# armwiz-board.net
KiCad netlist of a schematic drawn in EAGLE
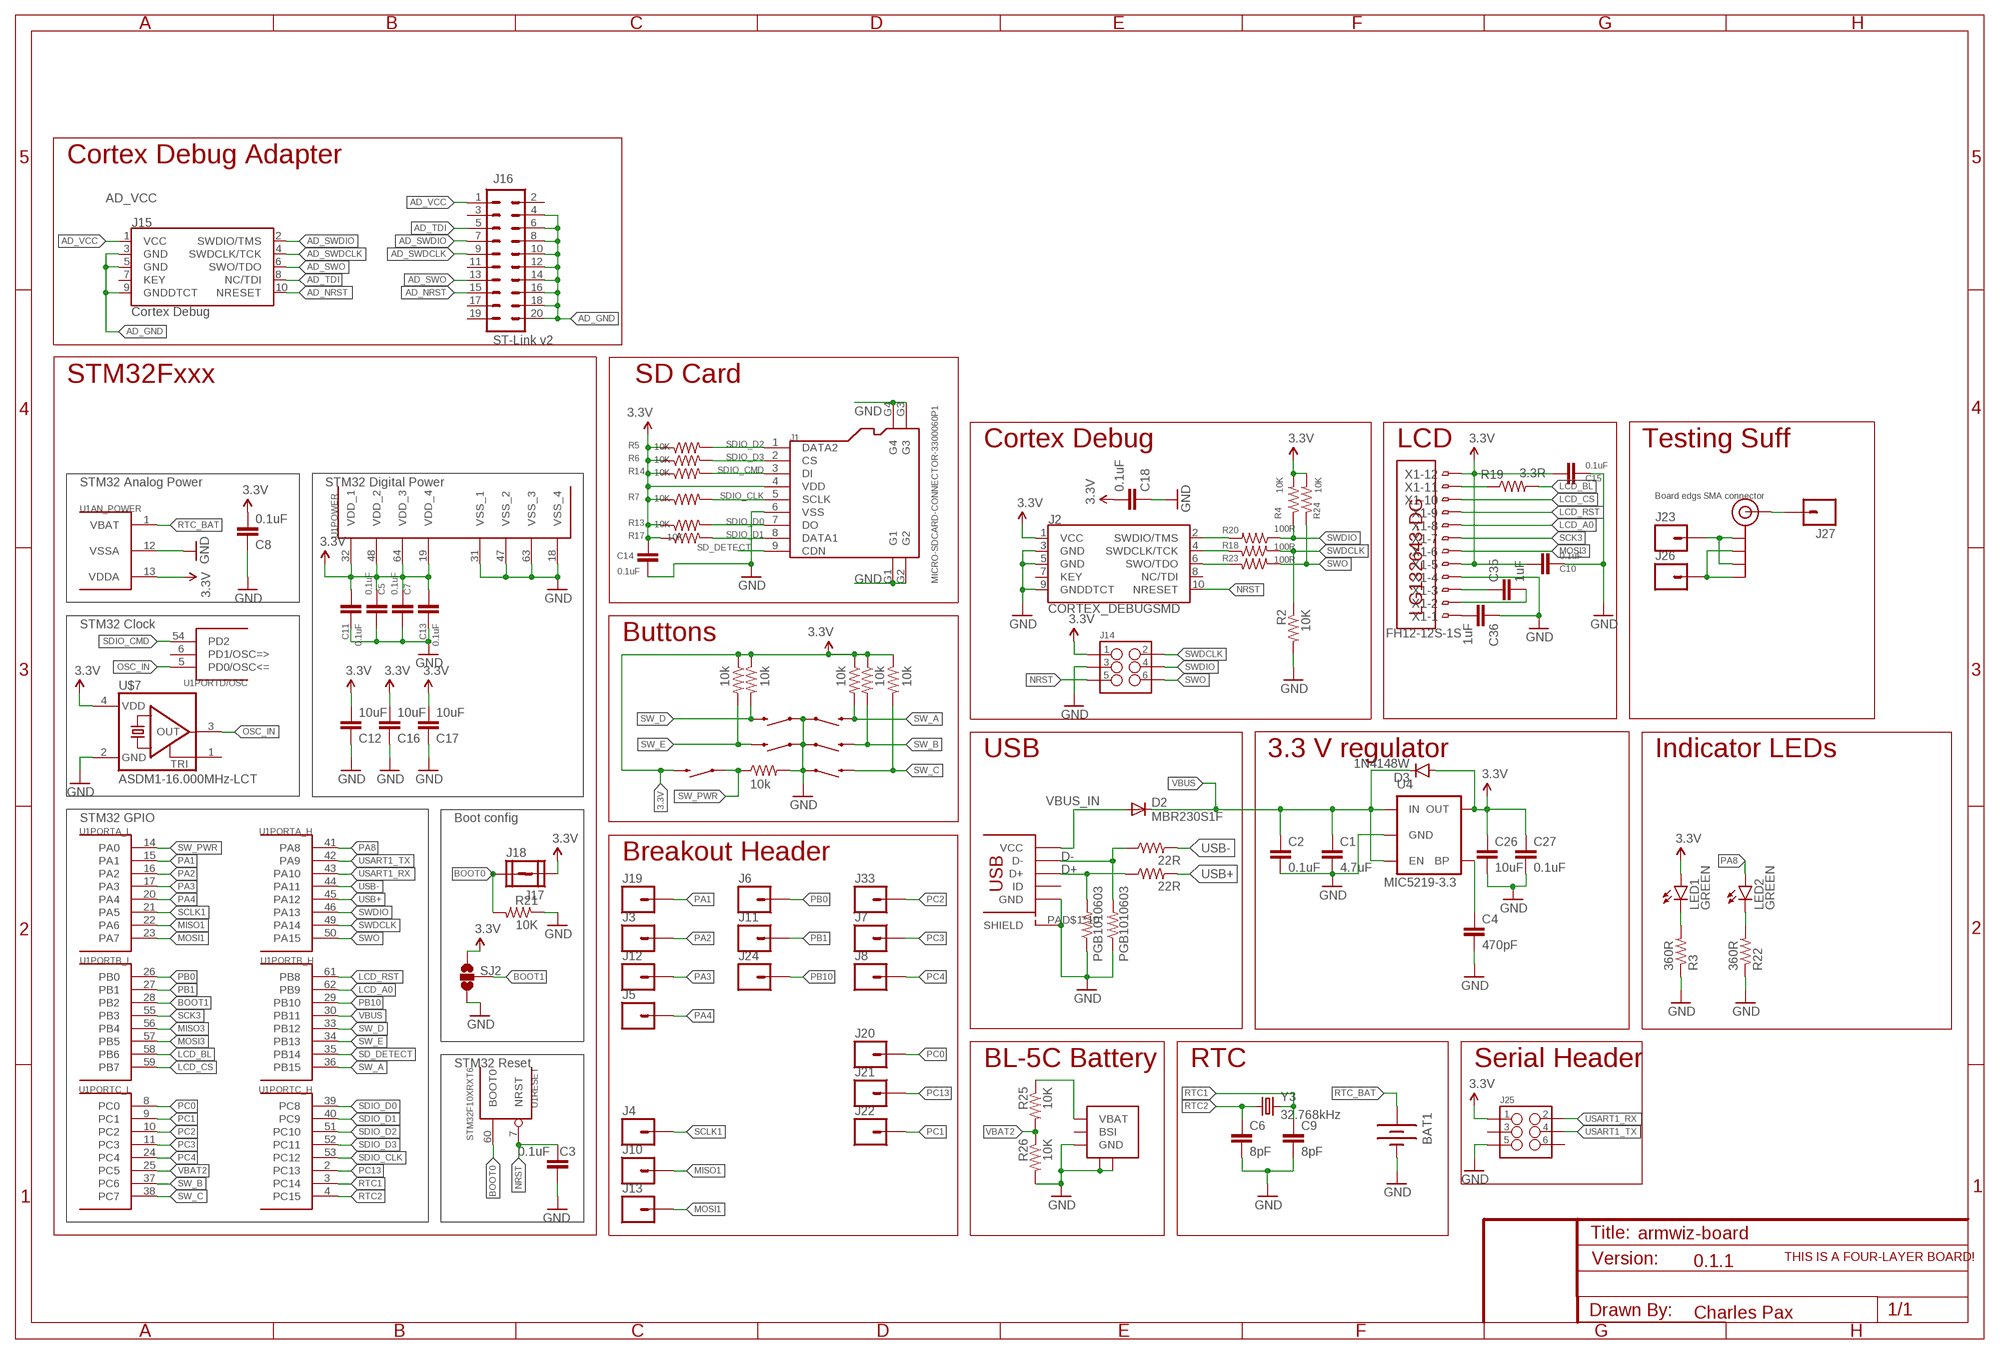
[diagram p0: schematic, sheet 1]

(export (version "E")
  (design (tool "Eeschema 10.0.6"))
  (components
    (comp (ref "BAT1")
      (value "BATTERY12MM")
      (footprint "eagle-import:BATTCON_12MM")
      (fields (field (name "MF") "Keystone Electronics") (field (name "MPN") "3000TR"))
      (libsource (lib "eagle-import") (part "BATTERY12MM"))
    )
    (comp (ref "C1")
      (value "4.7uF")
      (footprint "eagle-import:C0402K")
      (libsource (lib "eagle-import") (part "C-EUC0402K"))
    )
    (comp (ref "C2")
      (value "0.1uF")
      (footprint "eagle-import:C0402K")
      (libsource (lib "eagle-import") (part "C-EUC0402K"))
    )
    (comp (ref "C3")
      (value "0.1uF")
      (footprint "eagle-import:C0402K")
      (libsource (lib "eagle-import") (part "C-EUC0402K"))
    )
    (comp (ref "C4")
      (value "470pF")
      (footprint "eagle-import:C0402K")
      (libsource (lib "eagle-import") (part "C-EUC0402K"))
    )
    (comp (ref "C5")
      (value "0.1uF")
      (footprint "eagle-import:C0402K")
      (libsource (lib "eagle-import") (part "C-EUC0402K"))
    )
    (comp (ref "C6")
      (value "8pF")
      (footprint "eagle-import:C0402K")
      (libsource (lib "eagle-import") (part "C-EUC0402K"))
    )
    (comp (ref "C7")
      (value "0.1uF")
      (footprint "eagle-import:C0402K")
      (libsource (lib "eagle-import") (part "C-EUC0402K"))
    )
    (comp (ref "C8")
      (value "0.1uF")
      (footprint "eagle-import:C0402K")
      (libsource (lib "eagle-import") (part "C-EUC0402K"))
    )
    (comp (ref "C9")
      (value "8pF")
      (footprint "eagle-import:C0402K")
      (libsource (lib "eagle-import") (part "C-EUC0402K"))
    )
    (comp (ref "C10")
      (value "0.1uF")
      (footprint "eagle-import:C0402K")
      (libsource (lib "eagle-import") (part "C-EUC0402K"))
    )
    (comp (ref "C11")
      (value "0.1uF")
      (footprint "eagle-import:C0402K")
      (libsource (lib "eagle-import") (part "C-EUC0402K"))
    )
    (comp (ref "C12")
      (value "10uF")
      (footprint "eagle-import:C0402K")
      (libsource (lib "eagle-import") (part "C-EUC0402K"))
    )
    (comp (ref "C13")
      (value "0.1uF")
      (footprint "eagle-import:C0402K")
      (libsource (lib "eagle-import") (part "C-EUC0402K"))
    )
    (comp (ref "C14")
      (value "0.1uF")
      (footprint "eagle-import:C0402K")
      (libsource (lib "eagle-import") (part "C-EUC0402K"))
    )
    (comp (ref "C15")
      (value "0.1uF")
      (footprint "eagle-import:C0402K")
      (libsource (lib "eagle-import") (part "C-EUC0402K"))
    )
    (comp (ref "C16")
      (value "10uF")
      (footprint "eagle-import:C0402K")
      (libsource (lib "eagle-import") (part "C-EUC0402K"))
    )
    (comp (ref "C17")
      (value "10uF")
      (footprint "eagle-import:C0402K")
      (libsource (lib "eagle-import") (part "C-EUC0402K"))
    )
    (comp (ref "C18")
      (value "0.1uF")
      (footprint "eagle-import:C0402K")
      (libsource (lib "eagle-import") (part "C-EUC0402K"))
    )
    (comp (ref "C26")
      (value "10uF")
      (footprint "eagle-import:C0402K")
      (libsource (lib "eagle-import") (part "C-EUC0402K"))
    )
    (comp (ref "C27")
      (value "0.1uF")
      (footprint "eagle-import:C0402K")
      (libsource (lib "eagle-import") (part "C-EUC0402K"))
    )
    (comp (ref "C35")
      (value "1uF")
      (footprint "eagle-import:C0402K")
      (libsource (lib "eagle-import") (part "C-EUC0402K"))
    )
    (comp (ref "C36")
      (value "1uF")
      (footprint "eagle-import:C0402K")
      (libsource (lib "eagle-import") (part "C-EUC0402K"))
    )
    (comp (ref "D2")
      (value "MBR230S1F")
      (footprint "eagle-import:SOD123")
      (fields (field (name "MF") "DIODES INC") (field (name "MPN") "MBR230S1F-7"))
      (libsource (lib "eagle-import") (part "SPARKFUN-DISCRETESEMI_DIODESOD123SOD123"))
    )
    (comp (ref "D3")
      (value "1N4148W")
      (footprint "eagle-import:SOD-123")
      (libsource (lib "eagle-import") (part "DIODESOD123"))
    )
    (comp (ref "J$1")
      (value "SMA_EDGE")
      (footprint "eagle-import:SMA-EDGE")
      (libsource (lib "eagle-import") (part "SMA_EDGE"))
    )
    (comp (ref "J1")
      (value "MICRO-SDCARD-CONNECTOR-3300060P1")
      (footprint "eagle-import:9P-SMD-W-RING")
      (fields (field (name "MF") "SUNTECH") (field (name "MPN") "ST-TF-003A"))
      (libsource (lib "eagle-import") (part "MICRO-SDCARD-CONNECTOR-3300060P1"))
    )
    (comp (ref "J2")
      (value "CORTEX_DEBUGSMD")
      (footprint "eagle-import:SAMTECH_FTSH-105-01")
      (libsource (lib "eagle-import") (part "CORTEX_DEBUGSMD"))
    )
    (comp (ref "J3")
      (value "M01PTH")
      (footprint "eagle-import:1X01")
      (libsource (lib "eagle-import") (part "M01PTH"))
    )
    (comp (ref "J4")
      (value "M01PTH")
      (footprint "eagle-import:1X01")
      (libsource (lib "eagle-import") (part "M01PTH"))
    )
    (comp (ref "J5")
      (value "M01PTH")
      (footprint "eagle-import:1X01")
      (libsource (lib "eagle-import") (part "M01PTH"))
    )
    (comp (ref "J6")
      (value "M01PTH")
      (footprint "eagle-import:1X01")
      (libsource (lib "eagle-import") (part "M01PTH"))
    )
    (comp (ref "J7")
      (value "M01PTH")
      (footprint "eagle-import:1X01")
      (libsource (lib "eagle-import") (part "M01PTH"))
    )
    (comp (ref "J8")
      (value "M01PTH")
      (footprint "eagle-import:1X01")
      (libsource (lib "eagle-import") (part "M01PTH"))
    )
    (comp (ref "J10")
      (value "M01PTH")
      (footprint "eagle-import:1X01")
      (libsource (lib "eagle-import") (part "M01PTH"))
    )
    (comp (ref "J11")
      (value "M01PTH")
      (footprint "eagle-import:1X01")
      (libsource (lib "eagle-import") (part "M01PTH"))
    )
    (comp (ref "J12")
      (value "M01PTH")
      (footprint "eagle-import:1X01")
      (libsource (lib "eagle-import") (part "M01PTH"))
    )
    (comp (ref "J13")
      (value "M01PTH")
      (footprint "eagle-import:1X01")
      (libsource (lib "eagle-import") (part "M01PTH"))
    )
    (comp (ref "J14")
      (value "M03X2PAX")
      (footprint "eagle-import:CONNECTORS_2X3_SMT_POSTS_T400")
      (fields (field (name "MF") "FCI") (field (name "MPN") "95278-101A06LF"))
      (libsource (lib "eagle-import") (part "M03X2PAX"))
    )
    (comp (ref "J15")
      (value "Cortex Debug")
      (footprint "eagle-import:SAMTECH_FTSH-105-01")
      (libsource (lib "eagle-import") (part "CORTEX_DEBUGSMD"))
    )
    (comp (ref "J16")
      (value "ST-Link v2")
      (footprint "eagle-import:2X10")
      (libsource (lib "eagle-import") (part "M10X2"))
    )
    (comp (ref "J17")
      (value "M01NOSILK-KIT")
      (footprint "eagle-import:1X01NS-KIT")
      (libsource (lib "eagle-import") (part "M01NOSILK-KIT"))
    )
    (comp (ref "J18")
      (value "M01NOSILK-KIT")
      (footprint "eagle-import:1X01NS-KIT")
      (libsource (lib "eagle-import") (part "M01NOSILK-KIT"))
    )
    (comp (ref "J19")
      (value "M01PTH")
      (footprint "eagle-import:1X01")
      (libsource (lib "eagle-import") (part "M01PTH"))
    )
    (comp (ref "J20")
      (value "M01PTH")
      (footprint "eagle-import:1X01")
      (libsource (lib "eagle-import") (part "M01PTH"))
    )
    (comp (ref "J21")
      (value "M01PTH")
      (footprint "eagle-import:1X01")
      (libsource (lib "eagle-import") (part "M01PTH"))
    )
    (comp (ref "J22")
      (value "M01PTH")
      (footprint "eagle-import:1X01")
      (libsource (lib "eagle-import") (part "M01PTH"))
    )
    (comp (ref "J23")
      (value "M01PTH")
      (footprint "eagle-import:1X01")
      (libsource (lib "eagle-import") (part "M01PTH"))
    )
    (comp (ref "J24")
      (value "M01PTH")
      (footprint "eagle-import:1X01")
      (libsource (lib "eagle-import") (part "M01PTH"))
    )
    (comp (ref "J25")
      (value "M03X2PAX")
      (footprint "eagle-import:CONNECTORS_2X3_SMT_POSTS_T400")
      (fields (field (name "MF") "FCI") (field (name "MPN") "95278-101A06LF"))
      (libsource (lib "eagle-import") (part "M03X2PAX"))
    )
    (comp (ref "J26")
      (value "M01PTH")
      (footprint "eagle-import:1X01")
      (libsource (lib "eagle-import") (part "M01PTH"))
    )
    (comp (ref "J27")
      (value "M01PTH")
      (footprint "eagle-import:1X01")
      (libsource (lib "eagle-import") (part "M01PTH"))
    )
    (comp (ref "J33")
      (value "M01PTH")
      (footprint "eagle-import:1X01")
      (libsource (lib "eagle-import") (part "M01PTH"))
    )
    (comp (ref "LED1")
      (value "GREEN")
      (footprint "eagle-import:LED-0603")
      (libsource (lib "eagle-import") (part "LED0603"))
    )
    (comp (ref "LED2")
      (value "GREEN")
      (footprint "eagle-import:LED-0603")
      (libsource (lib "eagle-import") (part "LED0603"))
    )
    (comp (ref "R1")
      (value "10k")
      (footprint "eagle-import:R0402")
      (libsource (lib "eagle-import") (part "R-US_R0402"))
    )
    (comp (ref "R2")
      (value "10K")
      (footprint "eagle-import:R0402")
      (libsource (lib "eagle-import") (part "R-US_R0402"))
    )
    (comp (ref "R3")
      (value "360R")
      (footprint "eagle-import:R0402")
      (libsource (lib "eagle-import") (part "R-US_R0402"))
    )
    (comp (ref "R4")
      (value "10K")
      (footprint "eagle-import:R0402")
      (libsource (lib "eagle-import") (part "R-US_R0402"))
    )
    (comp (ref "R5")
      (value "10K")
      (footprint "eagle-import:R0402")
      (libsource (lib "eagle-import") (part "R-US_R0402"))
    )
    (comp (ref "R6")
      (value "10K")
      (footprint "eagle-import:R0402")
      (libsource (lib "eagle-import") (part "R-US_R0402"))
    )
    (comp (ref "R7")
      (value "10K")
      (footprint "eagle-import:R0402")
      (libsource (lib "eagle-import") (part "R-US_R0402"))
    )
    (comp (ref "R8")
      (value "10k")
      (footprint "eagle-import:R0402")
      (libsource (lib "eagle-import") (part "R-US_R0402"))
    )
    (comp (ref "R9")
      (value "22R")
      (footprint "eagle-import:R0402")
      (libsource (lib "eagle-import") (part "R-US_R0402"))
    )
    (comp (ref "R10")
      (value "22R")
      (footprint "eagle-import:R0402")
      (libsource (lib "eagle-import") (part "R-US_R0402"))
    )
    (comp (ref "R11")
      (value "10k")
      (footprint "eagle-import:R0402")
      (libsource (lib "eagle-import") (part "R-US_R0402"))
    )
    (comp (ref "R12")
      (value "10k")
      (footprint "eagle-import:R0402")
      (libsource (lib "eagle-import") (part "R-US_R0402"))
    )
    (comp (ref "R13")
      (value "10K")
      (footprint "eagle-import:R0402")
      (libsource (lib "eagle-import") (part "R-US_R0402"))
    )
    (comp (ref "R14")
      (value "10K")
      (footprint "eagle-import:R0402")
      (libsource (lib "eagle-import") (part "R-US_R0402"))
    )
    (comp (ref "R15")
      (value "10k")
      (footprint "eagle-import:R0402")
      (libsource (lib "eagle-import") (part "R-US_R0402"))
    )
    (comp (ref "R16")
      (value "10k")
      (footprint "eagle-import:R0402")
      (libsource (lib "eagle-import") (part "R-US_R0402"))
    )
    (comp (ref "R17")
      (value "10K")
      (footprint "eagle-import:R0402")
      (libsource (lib "eagle-import") (part "R-US_R0402"))
    )
    (comp (ref "R18")
      (value "100R")
      (footprint "eagle-import:R0402")
      (libsource (lib "eagle-import") (part "R-US_R0402"))
    )
    (comp (ref "R19")
      (value "3.3R")
      (footprint "eagle-import:R0402")
      (libsource (lib "eagle-import") (part "R-US_R0402"))
    )
    (comp (ref "R20")
      (value "100R")
      (footprint "eagle-import:R0402")
      (libsource (lib "eagle-import") (part "R-US_R0402"))
    )
    (comp (ref "R21")
      (value "10K")
      (footprint "eagle-import:R0402")
      (libsource (lib "eagle-import") (part "R-US_R0402"))
    )
    (comp (ref "R22")
      (value "360R")
      (footprint "eagle-import:R0402")
      (libsource (lib "eagle-import") (part "R-US_R0402"))
    )
    (comp (ref "R23")
      (value "100R")
      (footprint "eagle-import:R0402")
      (libsource (lib "eagle-import") (part "R-US_R0402"))
    )
    (comp (ref "R24")
      (value "10K")
      (footprint "eagle-import:R0402")
      (libsource (lib "eagle-import") (part "R-US_R0402"))
    )
    (comp (ref "R25")
      (value "10K")
      (footprint "eagle-import:R0402")
      (libsource (lib "eagle-import") (part "R-US_R0402"))
    )
    (comp (ref "R26")
      (value "10K")
      (footprint "eagle-import:R0402")
      (libsource (lib "eagle-import") (part "R-US_R0402"))
    )
    (comp (ref "S1")
      (value "SWITCH-MOMENTARY-2SMD")
      (footprint "eagle-import:TACTILE_SWITCH_SMD")
      (fields (field (name "MF") "C&K Components") (field (name "MPN") "RS-187R05A2-DS MT RT"))
      (libsource (lib "eagle-import") (part "SWITCH-MOMENTARY-2SMD"))
    )
    (comp (ref "S2")
      (value "SWITCH-MOMENTARY-2SMD")
      (footprint "eagle-import:TACTILE_SWITCH_SMD")
      (fields (field (name "MF") "C&K Components") (field (name "MPN") "RS-187R05A2-DS MT RT"))
      (libsource (lib "eagle-import") (part "SWITCH-MOMENTARY-2SMD"))
    )
    (comp (ref "S3")
      (value "SWITCH-MOMENTARY-2SMD")
      (footprint "eagle-import:TACTILE_SWITCH_SMD")
      (fields (field (name "MF") "C&K Components") (field (name "MPN") "RS-187R05A2-DS MT RT"))
      (libsource (lib "eagle-import") (part "SWITCH-MOMENTARY-2SMD"))
    )
    (comp (ref "S4")
      (value "SWITCH-MOMENTARY-2SMD")
      (footprint "eagle-import:TACTILE_SWITCH_SMD")
      (fields (field (name "MF") "C&K Components") (field (name "MPN") "RS-187R05A2-DS MT RT"))
      (libsource (lib "eagle-import") (part "SWITCH-MOMENTARY-2SMD"))
    )
    (comp (ref "S5")
      (value "SWITCH-MOMENTARY-2SMD")
      (footprint "eagle-import:TACTILE_SWITCH_SMD")
      (fields (field (name "MF") "C&K Components") (field (name "MPN") "RS-187R05A2-DS MT RT"))
      (libsource (lib "eagle-import") (part "SWITCH-MOMENTARY-2SMD"))
    )
    (comp (ref "S6")
      (value "SWITCH-MOMENTARY-2SMD")
      (footprint "eagle-import:TACTILE_SWITCH_SMD")
      (fields (field (name "MF") "C&K Components") (field (name "MPN") "RS-187R05A2-DS MT RT"))
      (libsource (lib "eagle-import") (part "SWITCH-MOMENTARY-2SMD"))
    )
    (comp (ref "SJ2")
      (value "SOLDERJUMPER_2WAYS")
      (footprint "eagle-import:SJ_3")
      (libsource (lib "eagle-import") (part "SOLDERJUMPER_2WAYS"))
    )
    (comp (ref "U$1")
      (value "USB_MICROSMT+THRUHULE")
      (footprint "eagle-import:USB_MICRO_THRUHOLE")
      (fields (field (name "MF") "FCI") (field (name "MPN") "10118194-0001LF"))
      (libsource (lib "eagle-import") (part "USB_MICROSMT+THRUHULE"))
    )
    (comp (ref "U$2")
      (value "FOUR_LAYER_WARNING")
      (footprint "eagle-import:FOUR_LAYER_WARNING")
      (libsource (lib "eagle-import") (part "FOUR_LAYER_WARNING"))
    )
    (comp (ref "U$3")
      (value "BL-5C-CONNECTOR")
      (footprint "eagle-import:BL-5C-CONNECTOR")
      (fields (field (name "MPN") "BC-4-3P (77H)"))
      (libsource (lib "eagle-import") (part "BL-5C-CONNECTOR"))
    )
    (comp (ref "U$5")
      (value "LG132643-DG")
      (footprint "eagle-import:LG132643-DG")
      (fields (field (name "MPN") "LG132643-DW"))
      (libsource (lib "eagle-import") (part "LG132643-DG"))
    )
    (comp (ref "U$7")
      (value "ASDM1-16.000MHz-LCT")
      (footprint "eagle-import:ASE")
      (libsource (lib "eagle-import") (part "ASE"))
    )
    (comp (ref "U1")
      (value "STM32F10XRXT6")
      (footprint "eagle-import:TQFP64")
      (libsource (lib "eagle-import") (part "STM32F10XRXT6"))
    )
    (comp (ref "U4")
      (value "MIC5219-3.3V")
      (footprint "eagle-import:SOT23-5")
      (fields (field (name "MF") "Micrel") (field (name "MPN") "MIC5219-3.3YM5 TR"))
      (libsource (lib "eagle-import") (part "V_REG_LDOSMD"))
    )
    (comp (ref "X1")
      (value "FH12-12S-1S")
      (footprint "eagle-import:FH12-12S-1SH")
      (fields (field (name "MF") "Hirose Connector") (field (name "MPN") "FH12-12S-1SH(55)"))
      (libsource (lib "eagle-import") (part "FH12-12S-1S"))
    )
    (comp (ref "Y3")
      (value "32.768kHz")
      (footprint "eagle-import:CRYSTAL-SMD-3.2X1.5MM")
      (libsource (lib "eagle-import") (part "CRYSTAL3.2X1.5MM"))
    )
    (comp (ref "Z1")
      (value "PGB1010603")
      (footprint "eagle-import:SPARKFUN-RESISTORS_0603-RES")
      (fields (field (name "MF") "Littelfuse") (field (name "MPN") "PGB1010603NRHF"))
      (libsource (lib "eagle-import") (part "SPARKFUN-RESISTORS_RESISTOR0603-RES"))
    )
    (comp (ref "Z2")
      (value "PGB1010603")
      (footprint "eagle-import:SPARKFUN-RESISTORS_0603-RES")
      (fields (field (name "MF") "Littelfuse") (field (name "MPN") "PGB1010603NRHF"))
      (libsource (lib "eagle-import") (part "SPARKFUN-RESISTORS_RESISTOR0603-RES"))
    )
  )
  (nets
    (net (code "1") (name "/D+") (class "Default")
      (node (ref "R9") (pin "1") (pinfunction "1_1") (pintype "passive"))
      (node (ref "U$1") (pin "PIN$3") (pinfunction "D+_PIN$3") (pintype "bidirectional"))
      (node (ref "Z1") (pin "2") (pinfunction "2_2") (pintype "passive"))
    )
    (net (code "2") (name "/D-") (class "Default")
      (node (ref "R10") (pin "1") (pinfunction "1_1") (pintype "passive"))
      (node (ref "U$1") (pin "PIN$2") (pinfunction "D-_PIN$2") (pintype "bidirectional"))
      (node (ref "Z2") (pin "2") (pinfunction "2_2") (pintype "passive"))
    )
    (net (code "3") (name "/VBUS_IN") (class "Default")
      (node (ref "D2") (pin "A") (pinfunction "A_A") (pintype "passive"))
      (node (ref "U$1") (pin "PIN$1") (pinfunction "VCC_PIN$1") (pintype "bidirectional"))
    )
    (net (code "4") (name "3.3V") (class "Default")
      (node (ref "C10") (pin "2") (pinfunction "2_2") (pintype "passive"))
      (node (ref "C11") (pin "2") (pinfunction "2_2") (pintype "passive"))
      (node (ref "C12") (pin "2") (pinfunction "2_2") (pintype "passive"))
      (node (ref "C13") (pin "2") (pinfunction "2_2") (pintype "passive"))
      (node (ref "C14") (pin "2") (pinfunction "2_2") (pintype "passive"))
      (node (ref "C15") (pin "2") (pinfunction "2_2") (pintype "passive"))
      (node (ref "C16") (pin "2") (pinfunction "2_2") (pintype "passive"))
      (node (ref "C17") (pin "2") (pinfunction "2_2") (pintype "passive"))
      (node (ref "C18") (pin "2") (pinfunction "2_2") (pintype "passive"))
      (node (ref "C26") (pin "1") (pinfunction "1_1") (pintype "passive"))
      (node (ref "C27") (pin "1") (pinfunction "1_1") (pintype "passive"))
      (node (ref "C5") (pin "1") (pinfunction "1_1") (pintype "passive"))
      (node (ref "C7") (pin "1") (pinfunction "1_1") (pintype "passive"))
      (node (ref "C8") (pin "2") (pinfunction "2_2") (pintype "passive"))
      (node (ref "D3") (pin "A") (pinfunction "A_A") (pintype "passive"))
      (node (ref "J1") (pin "4") (pinfunction "VDD_4") (pintype "bidirectional"))
      (node (ref "J14") (pin "1") (pinfunction "1_1") (pintype "bidirectional"))
      (node (ref "J18") (pin "1") (pinfunction "1_1") (pintype "passive"))
      (node (ref "J2") (pin "1") (pinfunction "VCC_1") (pintype "bidirectional"))
      (node (ref "J25") (pin "1") (pinfunction "1_1") (pintype "bidirectional"))
      (node (ref "LED1") (pin "A") (pinfunction "A_A") (pintype "passive"))
      (node (ref "R11") (pin "1") (pinfunction "1_1") (pintype "passive"))
      (node (ref "R12") (pin "1") (pinfunction "1_1") (pintype "passive"))
      (node (ref "R13") (pin "1") (pinfunction "1_1") (pintype "passive"))
      (node (ref "R14") (pin "1") (pinfunction "1_1") (pintype "passive"))
      (node (ref "R15") (pin "1") (pinfunction "1_1") (pintype "passive"))
      (node (ref "R16") (pin "1") (pinfunction "1_1") (pintype "passive"))
      (node (ref "R17") (pin "1") (pinfunction "1_1") (pintype "passive"))
      (node (ref "R24") (pin "2") (pinfunction "2_2") (pintype "passive"))
      (node (ref "R4") (pin "2") (pinfunction "2_2") (pintype "passive"))
      (node (ref "R5") (pin "1") (pinfunction "1_1") (pintype "passive"))
      (node (ref "R6") (pin "1") (pinfunction "1_1") (pintype "passive"))
      (node (ref "R7") (pin "1") (pinfunction "1_1") (pintype "passive"))
      (node (ref "R8") (pin "1") (pinfunction "1_1") (pintype "passive"))
      (node (ref "S6") (pin "3") (pinfunction "2_3") (pintype "passive"))
      (node (ref "SJ2") (pin "3") (pinfunction "3_3") (pintype "passive"))
      (node (ref "U$7") (pin "4") (pinfunction "VDD_4") (pintype "power_in"))
      (node (ref "U1") (pin "13") (pinfunction "VDDA_13") (pintype "power_in"))
      (node (ref "U1") (pin "19") (pinfunction "VDD_4_19") (pintype "power_in"))
      (node (ref "U1") (pin "32") (pinfunction "VDD_1_32") (pintype "power_in"))
      (node (ref "U1") (pin "48") (pinfunction "VDD_2_48") (pintype "power_in"))
      (node (ref "U1") (pin "64") (pinfunction "VDD_3_64") (pintype "power_in"))
      (node (ref "U4") (pin "5") (pinfunction "OUT_5") (pintype "passive"))
      (node (ref "X1") (pin "12") (pinfunction "1_12") (pintype "passive"))
      (node (ref "X1") (pin "5") (pinfunction "1_5") (pintype "passive"))
    )
    (net (code "5") (name "AD_GND") (class "Default")
      (node (ref "J15") (pin "3") (pinfunction "GND_3") (pintype "bidirectional"))
      (node (ref "J15") (pin "5") (pinfunction "GND_5") (pintype "bidirectional"))
      (node (ref "J15") (pin "9") (pinfunction "GNDDTCT_9") (pintype "bidirectional"))
      (node (ref "J16") (pin "10") (pinfunction "10_10") (pintype "passive"))
      (node (ref "J16") (pin "12") (pinfunction "12_12") (pintype "passive"))
      (node (ref "J16") (pin "14") (pinfunction "14_14") (pintype "passive"))
      (node (ref "J16") (pin "16") (pinfunction "16_16") (pintype "passive"))
      (node (ref "J16") (pin "18") (pinfunction "18_18") (pintype "passive"))
      (node (ref "J16") (pin "20") (pinfunction "20_20") (pintype "passive"))
      (node (ref "J16") (pin "4") (pinfunction "4_4") (pintype "passive"))
      (node (ref "J16") (pin "6") (pinfunction "6_6") (pintype "passive"))
      (node (ref "J16") (pin "8") (pinfunction "8_8") (pintype "passive"))
    )
    (net (code "6") (name "AD_NRST") (class "Default")
      (node (ref "J15") (pin "10") (pinfunction "NRESET_10") (pintype "bidirectional"))
      (node (ref "J16") (pin "15") (pinfunction "15_15") (pintype "passive"))
    )
    (net (code "7") (name "AD_SWDCLK") (class "Default")
      (node (ref "J15") (pin "4") (pinfunction "SWDCLK/TCK_4") (pintype "bidirectional"))
      (node (ref "J16") (pin "9") (pinfunction "9_9") (pintype "passive"))
    )
    (net (code "8") (name "AD_SWDIO") (class "Default")
      (node (ref "J15") (pin "2") (pinfunction "SWDIO/TMS_2") (pintype "bidirectional"))
      (node (ref "J16") (pin "7") (pinfunction "7_7") (pintype "passive"))
    )
    (net (code "9") (name "AD_SWO") (class "Default")
      (node (ref "J15") (pin "6") (pinfunction "SWO/TDO_6") (pintype "bidirectional"))
      (node (ref "J16") (pin "13") (pinfunction "13_13") (pintype "passive"))
    )
    (net (code "10") (name "AD_TDI") (class "Default")
      (node (ref "J15") (pin "8") (pinfunction "NC/TDI_8") (pintype "bidirectional"))
      (node (ref "J16") (pin "5") (pinfunction "5_5") (pintype "passive"))
    )
    (net (code "11") (name "AD_VCC") (class "Default")
      (node (ref "J15") (pin "1") (pinfunction "VCC_1") (pintype "bidirectional"))
      (node (ref "J16") (pin "1") (pinfunction "1_1") (pintype "passive"))
    )
    (net (code "12") (name "BOOT0") (class "Default")
      (node (ref "J17") (pin "1") (pinfunction "1_1") (pintype "passive"))
      (node (ref "R21") (pin "2") (pinfunction "2_2") (pintype "passive"))
      (node (ref "U1") (pin "60") (pinfunction "BOOT0_60") (pintype "input"))
    )
    (net (code "13") (name "BOOT1") (class "Default")
      (node (ref "SJ2") (pin "2") (pinfunction "2_2") (pintype "passive"))
      (node (ref "U1") (pin "28") (pinfunction "PB2_28") (pintype "bidirectional"))
    )
    (net (code "14") (name "GND") (class "Default")
      (node (ref "BAT1") (pin "GND") (pinfunction "-_GND") (pintype "power_in"))
      (node (ref "C1") (pin "2") (pinfunction "2_2") (pintype "passive"))
      (node (ref "C10") (pin "1") (pinfunction "1_1") (pintype "passive"))
      (node (ref "C11") (pin "1") (pinfunction "1_1") (pintype "passive"))
      (node (ref "C12") (pin "1") (pinfunction "1_1") (pintype "passive"))
      (node (ref "C13") (pin "1") (pinfunction "1_1") (pintype "passive"))
      (node (ref "C14") (pin "1") (pinfunction "1_1") (pintype "passive"))
      (node (ref "C15") (pin "1") (pinfunction "1_1") (pintype "passive"))
      (node (ref "C16") (pin "1") (pinfunction "1_1") (pintype "passive"))
      (node (ref "C17") (pin "1") (pinfunction "1_1") (pintype "passive"))
      (node (ref "C18") (pin "1") (pinfunction "1_1") (pintype "passive"))
      (node (ref "C2") (pin "2") (pinfunction "2_2") (pintype "passive"))
      (node (ref "C26") (pin "2") (pinfunction "2_2") (pintype "passive"))
      (node (ref "C27") (pin "2") (pinfunction "2_2") (pintype "passive"))
      (node (ref "C3") (pin "2") (pinfunction "2_2") (pintype "passive"))
      (node (ref "C36") (pin "1") (pinfunction "1_1") (pintype "passive"))
      (node (ref "C4") (pin "2") (pinfunction "2_2") (pintype "passive"))
      (node (ref "C5") (pin "2") (pinfunction "2_2") (pintype "passive"))
      (node (ref "C6") (pin "2") (pinfunction "2_2") (pintype "passive"))
      (node (ref "C7") (pin "2") (pinfunction "2_2") (pintype "passive"))
      (node (ref "C8") (pin "1") (pinfunction "1_1") (pintype "passive"))
      (node (ref "C9") (pin "2") (pinfunction "2_2") (pintype "passive"))
      (node (ref "J1") (pin "6") (pinfunction "VSS_6") (pintype "bidirectional"))
      (node (ref "J1") (pin "G1") (pinfunction "G1_G1") (pintype "bidirectional"))
      (node (ref "J1") (pin "G2") (pinfunction "G2_G2") (pintype "bidirectional"))
      (node (ref "J1") (pin "G3") (pinfunction "G3_G3") (pintype "bidirectional"))
      (node (ref "J1") (pin "G4") (pinfunction "G4_G4") (pintype "bidirectional"))
      (node (ref "J14") (pin "3") (pinfunction "3_3") (pintype "bidirectional"))
      (node (ref "J2") (pin "3") (pinfunction "GND_3") (pintype "bidirectional"))
      (node (ref "J2") (pin "5") (pinfunction "GND_5") (pintype "bidirectional"))
      (node (ref "J2") (pin "9") (pinfunction "GNDDTCT_9") (pintype "bidirectional"))
      (node (ref "J25") (pin "5") (pinfunction "5_5") (pintype "bidirectional"))
      (node (ref "R1") (pin "2") (pinfunction "2_2") (pintype "passive"))
      (node (ref "R2") (pin "2") (pinfunction "2_2") (pintype "passive"))
      (node (ref "R21") (pin "1") (pinfunction "1_1") (pintype "passive"))
      (node (ref "R22") (pin "1") (pinfunction "1_1") (pintype "passive"))
      (node (ref "R26") (pin "2") (pinfunction "2_2") (pintype "passive"))
      (node (ref "R3") (pin "1") (pinfunction "1_1") (pintype "passive"))
      (node (ref "S1") (pin "1") (pinfunction "1_1") (pintype "passive"))
      (node (ref "S2") (pin "1") (pinfunction "1_1") (pintype "passive"))
      (node (ref "S3") (pin "1") (pinfunction "1_1") (pintype "passive"))
      (node (ref "S4") (pin "1") (pinfunction "1_1") (pintype "passive"))
      (node (ref "S5") (pin "1") (pinfunction "1_1") (pintype "passive"))
      (node (ref "SJ2") (pin "1") (pinfunction "1_1") (pintype "passive"))
      (node (ref "U$1") (pin "PAD$1") (pinfunction "SHIELD_PAD$1") (pintype "bidirectional"))
      (node (ref "U$1") (pin "PAD$10") (pinfunction "SHIELD_PAD$10") (pintype "bidirectional"))
      (node (ref "U$1") (pin "PAD$2") (pinfunction "SHIELD_PAD$2") (pintype "bidirectional"))
      (node (ref "U$1") (pin "PAD$3") (pinfunction "SHIELD_PAD$3") (pintype "bidirectional"))
      (node (ref "U$1") (pin "PAD$4") (pinfunction "SHIELD_PAD$4") (pintype "bidirectional"))
      (node (ref "U$1") (pin "PAD$5") (pinfunction "SHIELD_PAD$5") (pintype "bidirectional"))
      (node (ref "U$1") (pin "PAD$6") (pinfunction "SHIELD_PAD$6") (pintype "bidirectional"))
      (node (ref "U$1") (pin "PAD$7") (pinfunction "SHIELD_PAD$7") (pintype "bidirectional"))
      (node (ref "U$1") (pin "PAD$8") (pinfunction "SHIELD_PAD$8") (pintype "bidirectional"))
      (node (ref "U$1") (pin "PAD$9") (pinfunction "SHIELD_PAD$9") (pintype "bidirectional"))
      (node (ref "U$1") (pin "PIN$5") (pinfunction "GND_PIN$5") (pintype "bidirectional"))
      (node (ref "U$3") (pin "P$3") (pinfunction "GND_P$3") (pintype "bidirectional"))
      (node (ref "U$3") (pin "P$4") (pinfunction "P$4_P$4") (pintype "bidirectional"))
      (node (ref "U$3") (pin "P$5") (pinfunction "P$5_P$5") (pintype "bidirectional"))
      (node (ref "U$7") (pin "2") (pinfunction "GND_2") (pintype "power_in"))
      (node (ref "U1") (pin "12") (pinfunction "VSSA_12") (pintype "power_in"))
      (node (ref "U1") (pin "18") (pinfunction "VSS_4_18") (pintype "power_in"))
      (node (ref "U1") (pin "31") (pinfunction "VSS_1_31") (pintype "power_in"))
      (node (ref "U1") (pin "47") (pinfunction "VSS_2_47") (pintype "power_in"))
      (node (ref "U1") (pin "63") (pinfunction "VSS_3_63") (pintype "power_in"))
      (node (ref "U4") (pin "2") (pinfunction "GND_2") (pintype "input"))
      (node (ref "X1") (pin "4") (pinfunction "1_4") (pintype "passive"))
      (node (ref "Z1") (pin "1") (pinfunction "1_1") (pintype "passive"))
      (node (ref "Z2") (pin "1") (pinfunction "1_1") (pintype "passive"))
    )
    (net (code "15") (name "LCD_A0") (class "Default")
      (node (ref "U1") (pin "62") (pinfunction "PB9_62") (pintype "bidirectional"))
      (node (ref "X1") (pin "8") (pinfunction "1_8") (pintype "passive"))
    )
    (net (code "16") (name "LCD_BL") (class "Default")
      (node (ref "R19") (pin "2") (pinfunction "2_2") (pintype "passive"))
      (node (ref "U1") (pin "58") (pinfunction "PB6_58") (pintype "bidirectional"))
    )
    (net (code "17") (name "LCD_CS") (class "Default")
      (node (ref "U1") (pin "59") (pinfunction "PB7_59") (pintype "bidirectional"))
      (node (ref "X1") (pin "10") (pinfunction "1_10") (pintype "passive"))
    )
    (net (code "18") (name "LCD_RST") (class "Default")
      (node (ref "U1") (pin "61") (pinfunction "PB8_61") (pintype "bidirectional"))
      (node (ref "X1") (pin "9") (pinfunction "1_9") (pintype "passive"))
    )
    (net (code "19") (name "MISO1") (class "Default")
      (node (ref "J10") (pin "1") (pinfunction "1_1") (pintype "passive"))
      (node (ref "U1") (pin "22") (pinfunction "PA6_22") (pintype "bidirectional"))
    )
    (net (code "20") (name "MISO3") (class "Default")
      (node (ref "U1") (pin "56") (pinfunction "PB4_56") (pintype "bidirectional"))
    )
    (net (code "21") (name "MOSI1") (class "Default")
      (node (ref "J13") (pin "1") (pinfunction "1_1") (pintype "passive"))
      (node (ref "U1") (pin "23") (pinfunction "PA7_23") (pintype "bidirectional"))
    )
    (net (code "22") (name "MOSI3") (class "Default")
      (node (ref "U1") (pin "57") (pinfunction "PB5_57") (pintype "bidirectional"))
      (node (ref "X1") (pin "6") (pinfunction "1_6") (pintype "passive"))
    )
    (net (code "23") (name "NRST") (class "Default")
      (node (ref "C3") (pin "1") (pinfunction "1_1") (pintype "passive"))
      (node (ref "J14") (pin "5") (pinfunction "5_5") (pintype "bidirectional"))
      (node (ref "J2") (pin "10") (pinfunction "NRESET_10") (pintype "bidirectional"))
      (node (ref "U1") (pin "7") (pinfunction "NRST_7") (pintype "input"))
    )
    (net (code "24") (name "Net-(C36-Pad2)") (class "Default")
      (node (ref "C36") (pin "2") (pinfunction "2_2") (pintype "passive"))
      (node (ref "X1") (pin "1") (pinfunction "1_1") (pintype "passive"))
    )
    (net (code "25") (name "Net-(J$1-GND-PadGND@0)") (class "Default")
      (node (ref "J$1") (pin "GND@0") (pinfunction "GND_GND@0") (pintype "bidirectional"))
      (node (ref "J$1") (pin "GND@2") (pinfunction "GND_GND@2") (pintype "bidirectional"))
      (node (ref "J23") (pin "1") (pinfunction "1_1") (pintype "passive"))
    )
    (net (code "26") (name "Net-(J$1-GND-PadGND@1)") (class "Default")
      (node (ref "J$1") (pin "GND@1") (pinfunction "GND_GND@1") (pintype "bidirectional"))
      (node (ref "J$1") (pin "GND@3") (pinfunction "GND_GND@3") (pintype "bidirectional"))
      (node (ref "J26") (pin "1") (pinfunction "1_1") (pintype "passive"))
    )
    (net (code "27") (name "Net-(J$1-SIGNAL)") (class "Default")
      (node (ref "J$1") (pin "SIG") (pinfunction "SIGNAL_SIG") (pintype "bidirectional"))
      (node (ref "J27") (pin "1") (pinfunction "1_1") (pintype "passive"))
    )
    (net (code "28") (name "Net-(J2-SWDCLK{slash}TCK)") (class "Default")
      (node (ref "J2") (pin "4") (pinfunction "SWDCLK/TCK_4") (pintype "bidirectional"))
      (node (ref "R18") (pin "2") (pinfunction "2_2") (pintype "passive"))
    )
    (net (code "29") (name "Net-(J2-SWDIO{slash}TMS)") (class "Default")
      (node (ref "J2") (pin "2") (pinfunction "SWDIO/TMS_2") (pintype "bidirectional"))
      (node (ref "R20") (pin "2") (pinfunction "2_2") (pintype "passive"))
    )
    (net (code "30") (name "Net-(J2-SWO{slash}TDO)") (class "Default")
      (node (ref "J2") (pin "6") (pinfunction "SWO/TDO_6") (pintype "bidirectional"))
      (node (ref "R23") (pin "2") (pinfunction "2_2") (pintype "passive"))
    )
    (net (code "31") (name "Net-(LED1-PadC)") (class "Default")
      (node (ref "LED1") (pin "C") (pinfunction "C_C") (pintype "passive"))
      (node (ref "R3") (pin "2") (pinfunction "2_2") (pintype "passive"))
    )
    (net (code "32") (name "Net-(LED2-PadC)") (class "Default")
      (node (ref "LED2") (pin "C") (pinfunction "C_C") (pintype "passive"))
      (node (ref "R22") (pin "2") (pinfunction "2_2") (pintype "passive"))
    )
    (net (code "33") (name "Net-(U$3-VBAT)") (class "Default")
      (node (ref "R25") (pin "1") (pinfunction "1_1") (pintype "passive"))
      (node (ref "U$3") (pin "P$1") (pinfunction "VBAT_P$1") (pintype "bidirectional"))
    )
    (net (code "34") (name "Net-(U4-BP)") (class "Default")
      (node (ref "C4") (pin "1") (pinfunction "1_1") (pintype "passive"))
      (node (ref "U4") (pin "4") (pinfunction "BP_4") (pintype "input"))
    )
    (net (code "35") (name "Net-(X1C-1)") (class "Default")
      (node (ref "R19") (pin "1") (pinfunction "1_1") (pintype "passive"))
      (node (ref "X1") (pin "11") (pinfunction "1_11") (pintype "passive"))
    )
    (net (code "36") (name "Net-(X1E-1)") (class "Default")
      (node (ref "C35") (pin "2") (pinfunction "2_2") (pintype "passive"))
      (node (ref "X1") (pin "2") (pinfunction "1_2") (pintype "passive"))
    )
    (net (code "37") (name "Net-(X1F-1)") (class "Default")
      (node (ref "C35") (pin "1") (pinfunction "1_1") (pintype "passive"))
      (node (ref "X1") (pin "3") (pinfunction "1_3") (pintype "passive"))
    )
    (net (code "38") (name "OSC_IN") (class "Default")
      (node (ref "U$7") (pin "3") (pinfunction "OUT_3") (pintype "output"))
      (node (ref "U1") (pin "5") (pinfunction "PD0/OSC<=_5") (pintype "bidirectional"))
    )
    (net (code "39") (name "PA1") (class "Default")
      (node (ref "J19") (pin "1") (pinfunction "1_1") (pintype "passive"))
      (node (ref "U1") (pin "15") (pinfunction "PA1_15") (pintype "bidirectional"))
    )
    (net (code "40") (name "PA2") (class "Default")
      (node (ref "J3") (pin "1") (pinfunction "1_1") (pintype "passive"))
      (node (ref "U1") (pin "16") (pinfunction "PA2_16") (pintype "bidirectional"))
    )
    (net (code "41") (name "PA3") (class "Default")
      (node (ref "J12") (pin "1") (pinfunction "1_1") (pintype "passive"))
      (node (ref "U1") (pin "17") (pinfunction "PA3_17") (pintype "bidirectional"))
    )
    (net (code "42") (name "PA4") (class "Default")
      (node (ref "J5") (pin "1") (pinfunction "1_1") (pintype "passive"))
      (node (ref "U1") (pin "20") (pinfunction "PA4_20") (pintype "bidirectional"))
    )
    (net (code "43") (name "PA8") (class "Default")
      (node (ref "LED2") (pin "A") (pinfunction "A_A") (pintype "passive"))
      (node (ref "U1") (pin "41") (pinfunction "PA8_41") (pintype "bidirectional"))
    )
    (net (code "44") (name "PB0") (class "Default")
      (node (ref "J6") (pin "1") (pinfunction "1_1") (pintype "passive"))
      (node (ref "U1") (pin "26") (pinfunction "PB0_26") (pintype "bidirectional"))
    )
    (net (code "45") (name "PB1") (class "Default")
      (node (ref "J11") (pin "1") (pinfunction "1_1") (pintype "passive"))
      (node (ref "U1") (pin "27") (pinfunction "PB1_27") (pintype "bidirectional"))
    )
    (net (code "46") (name "PB10") (class "Default")
      (node (ref "J24") (pin "1") (pinfunction "1_1") (pintype "passive"))
      (node (ref "U1") (pin "29") (pinfunction "PB10_29") (pintype "bidirectional"))
    )
    (net (code "47") (name "PC0") (class "Default")
      (node (ref "J20") (pin "1") (pinfunction "1_1") (pintype "passive"))
      (node (ref "U1") (pin "8") (pinfunction "PC0_8") (pintype "bidirectional"))
    )
    (net (code "48") (name "PC1") (class "Default")
      (node (ref "J22") (pin "1") (pinfunction "1_1") (pintype "passive"))
      (node (ref "U1") (pin "9") (pinfunction "PC1_9") (pintype "bidirectional"))
    )
    (net (code "49") (name "PC2") (class "Default")
      (node (ref "J33") (pin "1") (pinfunction "1_1") (pintype "passive"))
      (node (ref "U1") (pin "10") (pinfunction "PC2_10") (pintype "bidirectional"))
    )
    (net (code "50") (name "PC3") (class "Default")
      (node (ref "J7") (pin "1") (pinfunction "1_1") (pintype "passive"))
      (node (ref "U1") (pin "11") (pinfunction "PC3_11") (pintype "bidirectional"))
    )
    (net (code "51") (name "PC4") (class "Default")
      (node (ref "J8") (pin "1") (pinfunction "1_1") (pintype "passive"))
      (node (ref "U1") (pin "24") (pinfunction "PC4_24") (pintype "bidirectional"))
    )
    (net (code "52") (name "PC13") (class "Default")
      (node (ref "J21") (pin "1") (pinfunction "1_1") (pintype "passive"))
      (node (ref "U1") (pin "2") (pinfunction "PC13_2") (pintype "bidirectional"))
    )
    (net (code "53") (name "RTC1") (class "Default")
      (node (ref "C9") (pin "1") (pinfunction "1_1") (pintype "passive"))
      (node (ref "U1") (pin "3") (pinfunction "PC14_3") (pintype "bidirectional"))
      (node (ref "Y3") (pin "P$2") (pinfunction "2_P$2") (pintype "passive"))
    )
    (net (code "54") (name "RTC2") (class "Default")
      (node (ref "C6") (pin "1") (pinfunction "1_1") (pintype "passive"))
      (node (ref "U1") (pin "4") (pinfunction "PC15_4") (pintype "bidirectional"))
      (node (ref "Y3") (pin "P$1") (pinfunction "1_P$1") (pintype "passive"))
    )
    (net (code "55") (name "RTC_BAT") (class "Default")
      (node (ref "BAT1") (pin "PWR@1") (pinfunction "+_PWR@1") (pintype "power_in"))
      (node (ref "U1") (pin "1") (pinfunction "VBAT_1") (pintype "power_in"))
    )
    (net (code "56") (name "SCK3") (class "Default")
      (node (ref "U1") (pin "55") (pinfunction "PB3_55") (pintype "bidirectional"))
      (node (ref "X1") (pin "7") (pinfunction "1_7") (pintype "passive"))
    )
    (net (code "57") (name "SCLK1") (class "Default")
      (node (ref "J4") (pin "1") (pinfunction "1_1") (pintype "passive"))
      (node (ref "U1") (pin "21") (pinfunction "PA5_21") (pintype "bidirectional"))
    )
    (net (code "58") (name "SDIO_CLK") (class "Default")
      (node (ref "J1") (pin "5") (pinfunction "SCLK_5") (pintype "bidirectional"))
      (node (ref "R7") (pin "2") (pinfunction "2_2") (pintype "passive"))
      (node (ref "U1") (pin "53") (pinfunction "PC12_53") (pintype "bidirectional"))
    )
    (net (code "59") (name "SDIO_CMD") (class "Default")
      (node (ref "J1") (pin "3") (pinfunction "DI_3") (pintype "bidirectional"))
      (node (ref "R14") (pin "2") (pinfunction "2_2") (pintype "passive"))
      (node (ref "U1") (pin "54") (pinfunction "PD2_54") (pintype "bidirectional"))
    )
    (net (code "60") (name "SDIO_D0") (class "Default")
      (node (ref "J1") (pin "7") (pinfunction "DO_7") (pintype "bidirectional"))
      (node (ref "R13") (pin "2") (pinfunction "2_2") (pintype "passive"))
      (node (ref "U1") (pin "39") (pinfunction "PC8_39") (pintype "bidirectional"))
    )
    (net (code "61") (name "SDIO_D1") (class "Default")
      (node (ref "J1") (pin "8") (pinfunction "DATA1_8") (pintype "bidirectional"))
      (node (ref "R17") (pin "2") (pinfunction "2_2") (pintype "passive"))
      (node (ref "U1") (pin "40") (pinfunction "PC9_40") (pintype "bidirectional"))
    )
    (net (code "62") (name "SDIO_D2") (class "Default")
      (node (ref "J1") (pin "1") (pinfunction "DATA2_1") (pintype "bidirectional"))
      (node (ref "R5") (pin "2") (pinfunction "2_2") (pintype "passive"))
      (node (ref "U1") (pin "51") (pinfunction "PC10_51") (pintype "bidirectional"))
    )
    (net (code "63") (name "SDIO_D3") (class "Default")
      (node (ref "J1") (pin "2") (pinfunction "CS_2") (pintype "bidirectional"))
      (node (ref "R6") (pin "2") (pinfunction "2_2") (pintype "passive"))
      (node (ref "U1") (pin "52") (pinfunction "PC11_52") (pintype "bidirectional"))
    )
    (net (code "64") (name "SD_DETECT") (class "Default")
      (node (ref "J1") (pin "9") (pinfunction "CDN_9") (pintype "bidirectional"))
      (node (ref "U1") (pin "35") (pinfunction "PB14_35") (pintype "bidirectional"))
    )
    (net (code "65") (name "SWDCLK") (class "Default")
      (node (ref "J14") (pin "2") (pinfunction "2_2") (pintype "bidirectional"))
      (node (ref "R18") (pin "1") (pinfunction "1_1") (pintype "passive"))
      (node (ref "R2") (pin "1") (pinfunction "1_1") (pintype "passive"))
      (node (ref "U1") (pin "49") (pinfunction "PA14_49") (pintype "bidirectional"))
    )
    (net (code "66") (name "SWDIO") (class "Default")
      (node (ref "J14") (pin "4") (pinfunction "4_4") (pintype "bidirectional"))
      (node (ref "R20") (pin "1") (pinfunction "1_1") (pintype "passive"))
      (node (ref "R4") (pin "1") (pinfunction "1_1") (pintype "passive"))
      (node (ref "U1") (pin "46") (pinfunction "PA13_46") (pintype "bidirectional"))
    )
    (net (code "67") (name "SWO") (class "Default")
      (node (ref "J14") (pin "6") (pinfunction "6_6") (pintype "bidirectional"))
      (node (ref "R23") (pin "1") (pinfunction "1_1") (pintype "passive"))
      (node (ref "R24") (pin "1") (pinfunction "1_1") (pintype "passive"))
      (node (ref "U1") (pin "50") (pinfunction "PA15_50") (pintype "bidirectional"))
    )
    (net (code "68") (name "SW_A") (class "Default")
      (node (ref "R8") (pin "2") (pinfunction "2_2") (pintype "passive"))
      (node (ref "S3") (pin "3") (pinfunction "2_3") (pintype "passive"))
      (node (ref "U1") (pin "36") (pinfunction "PB15_36") (pintype "bidirectional"))
    )
    (net (code "69") (name "SW_B") (class "Default")
      (node (ref "R11") (pin "2") (pinfunction "2_2") (pintype "passive"))
      (node (ref "S2") (pin "3") (pinfunction "2_3") (pintype "passive"))
      (node (ref "U1") (pin "37") (pinfunction "PC6_37") (pintype "bidirectional"))
    )
    (net (code "70") (name "SW_C") (class "Default")
      (node (ref "R12") (pin "2") (pinfunction "2_2") (pintype "passive"))
      (node (ref "S1") (pin "3") (pinfunction "2_3") (pintype "passive"))
      (node (ref "U1") (pin "38") (pinfunction "PC7_38") (pintype "bidirectional"))
    )
    (net (code "71") (name "SW_D") (class "Default")
      (node (ref "R15") (pin "2") (pinfunction "2_2") (pintype "passive"))
      (node (ref "S4") (pin "3") (pinfunction "2_3") (pintype "passive"))
      (node (ref "U1") (pin "33") (pinfunction "PB12_33") (pintype "bidirectional"))
    )
    (net (code "72") (name "SW_E") (class "Default")
      (node (ref "R16") (pin "2") (pinfunction "2_2") (pintype "passive"))
      (node (ref "S5") (pin "3") (pinfunction "2_3") (pintype "passive"))
      (node (ref "U1") (pin "34") (pinfunction "PB13_34") (pintype "bidirectional"))
    )
    (net (code "73") (name "SW_PWR") (class "Default")
      (node (ref "R1") (pin "1") (pinfunction "1_1") (pintype "passive"))
      (node (ref "S6") (pin "1") (pinfunction "1_1") (pintype "passive"))
      (node (ref "U1") (pin "14") (pinfunction "PA0_14") (pintype "bidirectional"))
    )
    (net (code "74") (name "USART1_RX") (class "Default")
      (node (ref "J25") (pin "2") (pinfunction "2_2") (pintype "bidirectional"))
      (node (ref "U1") (pin "43") (pinfunction "PA10_43") (pintype "bidirectional"))
    )
    (net (code "75") (name "USART1_TX") (class "Default")
      (node (ref "J25") (pin "4") (pinfunction "4_4") (pintype "bidirectional"))
      (node (ref "U1") (pin "42") (pinfunction "PA9_42") (pintype "bidirectional"))
    )
    (net (code "76") (name "USB+") (class "Default")
      (node (ref "R9") (pin "2") (pinfunction "2_2") (pintype "passive"))
      (node (ref "U1") (pin "45") (pinfunction "PA12_45") (pintype "bidirectional"))
    )
    (net (code "77") (name "USB-") (class "Default")
      (node (ref "R10") (pin "2") (pinfunction "2_2") (pintype "passive"))
      (node (ref "U1") (pin "44") (pinfunction "PA11_44") (pintype "bidirectional"))
    )
    (net (code "78") (name "VBAT2") (class "Default")
      (node (ref "R25") (pin "2") (pinfunction "2_2") (pintype "passive"))
      (node (ref "R26") (pin "1") (pinfunction "1_1") (pintype "passive"))
      (node (ref "U1") (pin "25") (pinfunction "PC5_25") (pintype "bidirectional"))
    )
    (net (code "79") (name "VBUS") (class "Default")
      (node (ref "C1") (pin "1") (pinfunction "1_1") (pintype "passive"))
      (node (ref "C2") (pin "1") (pinfunction "1_1") (pintype "passive"))
      (node (ref "D2") (pin "C") (pinfunction "C_C") (pintype "passive"))
      (node (ref "D3") (pin "C") (pinfunction "C_C") (pintype "passive"))
      (node (ref "U1") (pin "30") (pinfunction "PB11_30") (pintype "bidirectional"))
      (node (ref "U4") (pin "1") (pinfunction "IN_1") (pintype "input"))
      (node (ref "U4") (pin "3") (pinfunction "EN_3") (pintype "input"))
    )
    (net (code "80") (name "unconnected-(J2-KEY-Pad7)") (class "Default")
      (node (ref "J2") (pin "7") (pinfunction "KEY_7") (pintype "bidirectional"))
    )
    (net (code "81") (name "unconnected-(J2-NC{slash}TDI-Pad8)") (class "Default")
      (node (ref "J2") (pin "8") (pinfunction "NC/TDI_8") (pintype "bidirectional"))
    )
    (net (code "82") (name "unconnected-(J15-KEY-Pad7)") (class "Default")
      (node (ref "J15") (pin "7") (pinfunction "KEY_7") (pintype "bidirectional"))
    )
    (net (code "83") (name "unconnected-(J16-Pad2)") (class "Default")
      (node (ref "J16") (pin "2") (pinfunction "2_2") (pintype "passive"))
    )
    (net (code "84") (name "unconnected-(J16-Pad3)") (class "Default")
      (node (ref "J16") (pin "3") (pinfunction "3_3") (pintype "passive"))
    )
    (net (code "85") (name "unconnected-(J16-Pad11)") (class "Default")
      (node (ref "J16") (pin "11") (pinfunction "11_11") (pintype "passive"))
    )
    (net (code "86") (name "unconnected-(J16-Pad17)") (class "Default")
      (node (ref "J16") (pin "17") (pinfunction "17_17") (pintype "passive"))
    )
    (net (code "87") (name "unconnected-(J16-Pad19)") (class "Default")
      (node (ref "J16") (pin "19") (pinfunction "19_19") (pintype "passive"))
    )
    (net (code "88") (name "unconnected-(J25-Pad3)") (class "Default")
      (node (ref "J25") (pin "3") (pinfunction "3_3") (pintype "bidirectional"))
    )
    (net (code "89") (name "unconnected-(J25-Pad6)") (class "Default")
      (node (ref "J25") (pin "6") (pinfunction "6_6") (pintype "bidirectional"))
    )
    (net (code "90") (name "unconnected-(U$1-ID-PadPIN$4)") (class "Default")
      (node (ref "U$1") (pin "PIN$4") (pinfunction "ID_PIN$4") (pintype "bidirectional"))
    )
    (net (code "91") (name "unconnected-(U$3-BSI-PadP$2)") (class "Default")
      (node (ref "U$3") (pin "P$2") (pinfunction "BSI_P$2") (pintype "bidirectional"))
    )
    (net (code "92") (name "unconnected-(U$7-TRI-Pad1)") (class "Default")
      (node (ref "U$7") (pin "1") (pinfunction "TRI_1") (pintype "input"))
    )
    (net (code "93") (name "unconnected-(U1H-PD1{slash}OSC=>-Pad6)") (class "Default")
      (node (ref "U1") (pin "6") (pinfunction "PD1/OSC=>_6") (pintype "bidirectional"))
    )
  )
)
